# MCU.net
KiCad netlist of a schematic drawn in Altium Designer
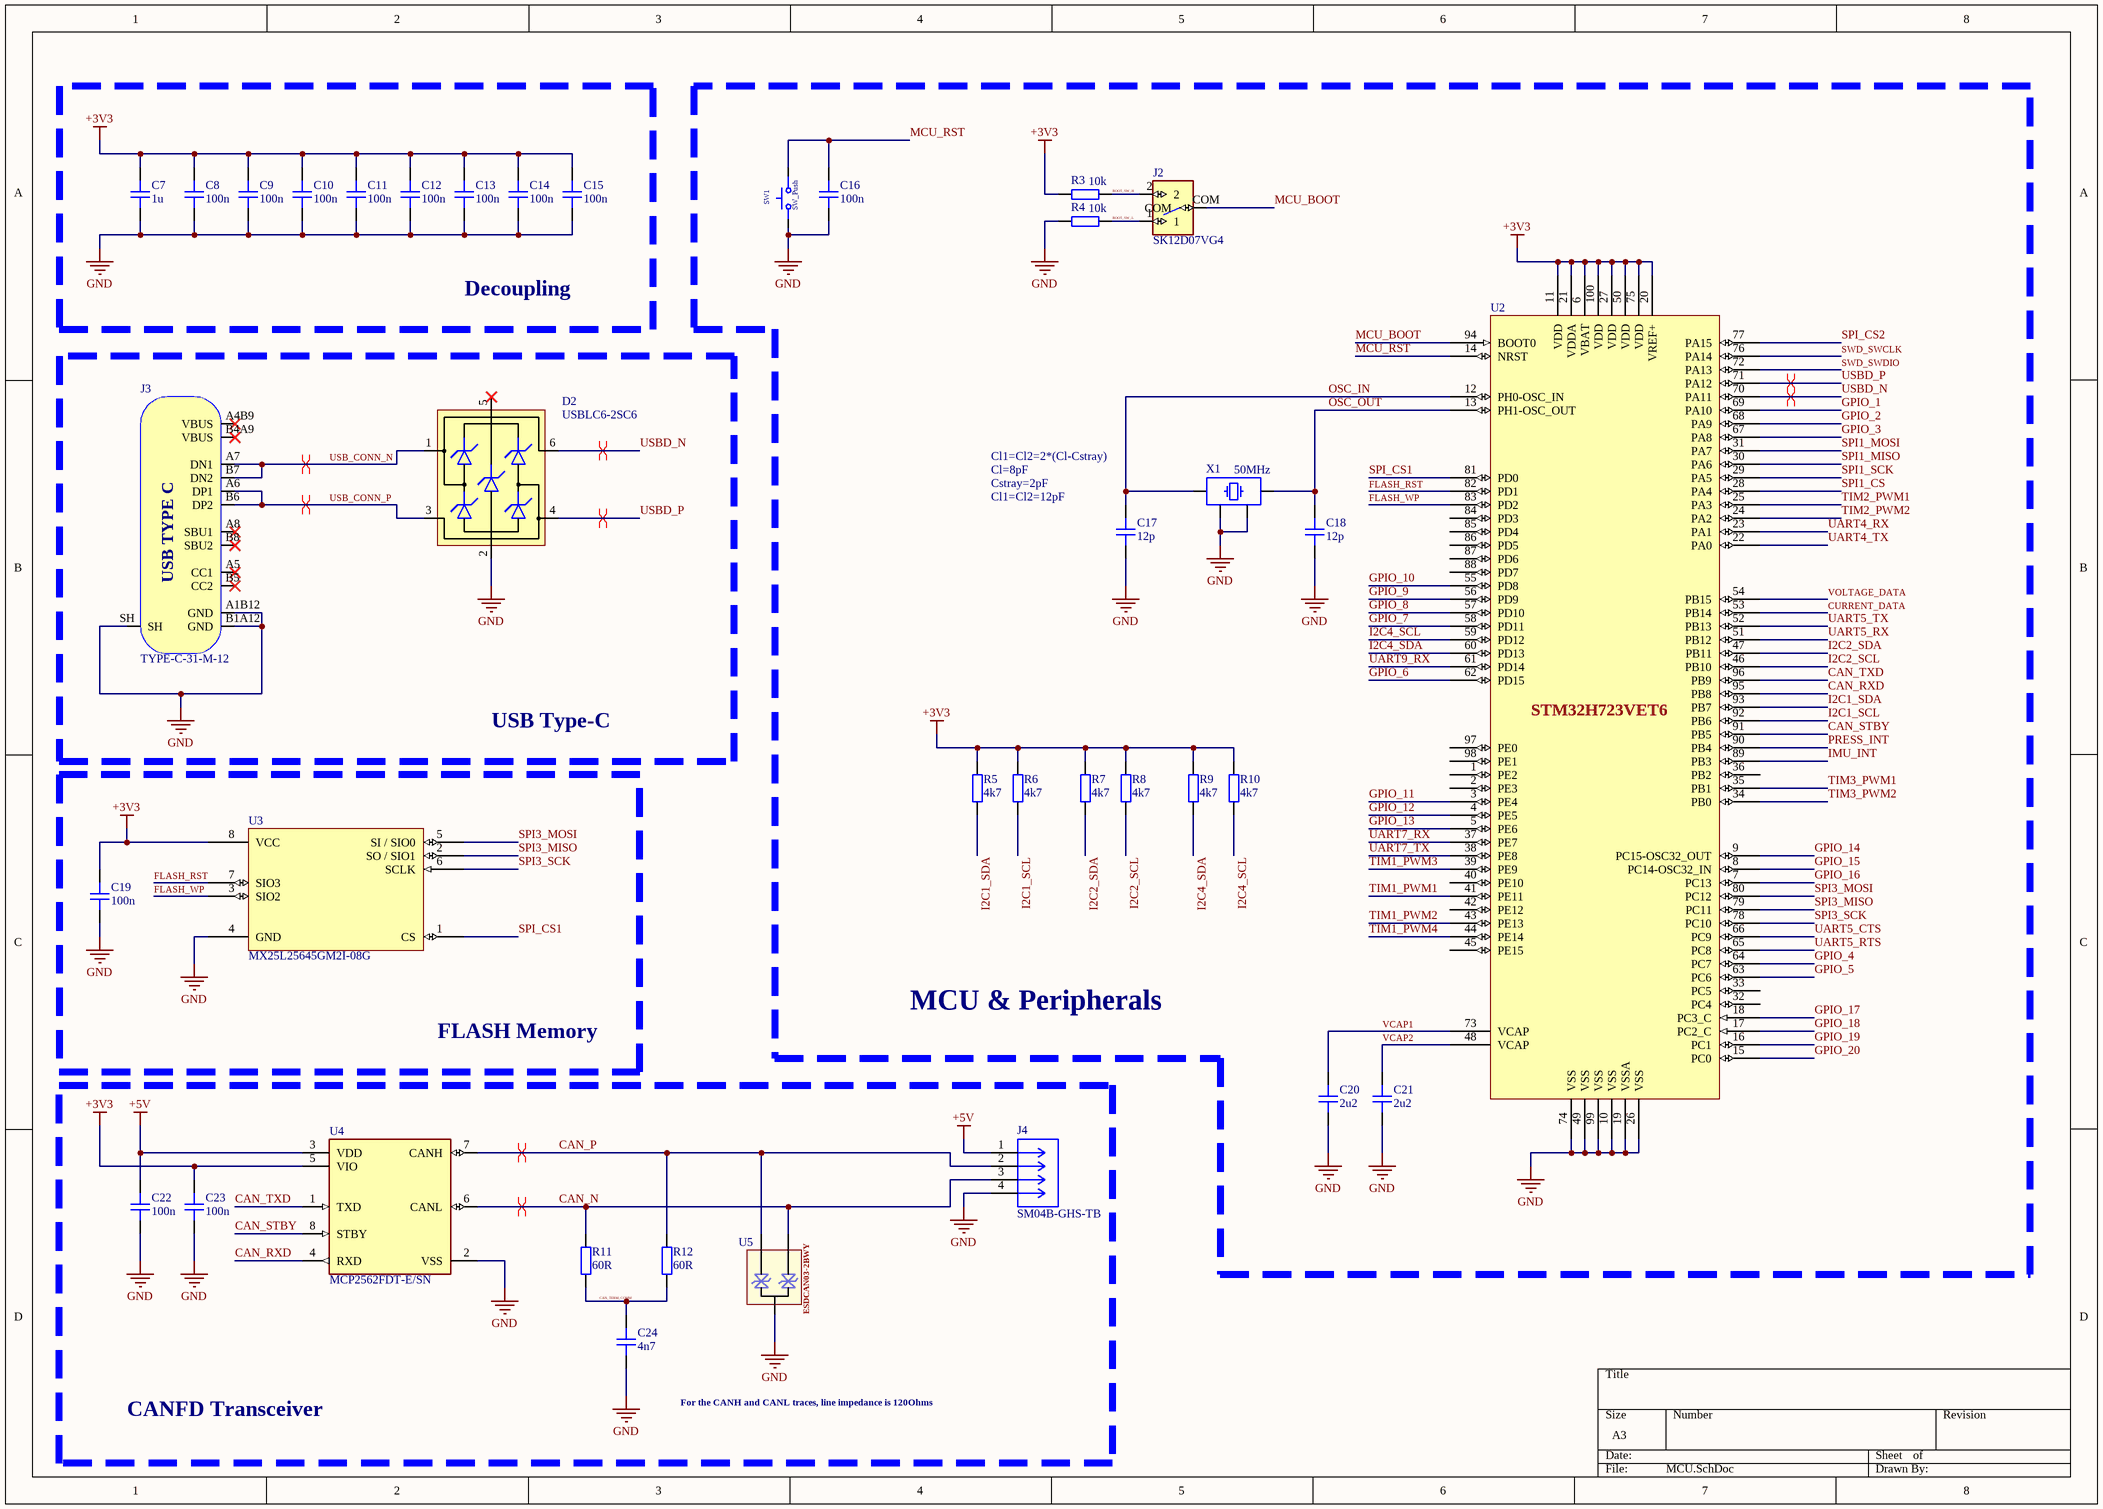
[diagram p0: MCU.SchDoc]

(export (version "E")
  (design (tool "Eeschema 10.0.6"))
  (components
    (comp (ref "C7")
      (value "1u")
      (footprint "CAP_0402")
      (description "Capacitor SMD 0402")
      (libsource (lib "Schematic-Lib-PhilsLab") (part "CAP_0402"))
    )
    (comp (ref "C8")
      (value "100n")
      (footprint "CAP_0402")
      (description "Capacitor SMD 0402")
      (libsource (lib "Schematic-Lib-PhilsLab") (part "CAP_0402"))
    )
    (comp (ref "C9")
      (value "100n")
      (footprint "CAP_0402")
      (description "Capacitor SMD 0402")
      (libsource (lib "Schematic-Lib-PhilsLab") (part "CAP_0402"))
    )
    (comp (ref "C10")
      (value "100n")
      (footprint "CAP_0402")
      (description "Capacitor SMD 0402")
      (libsource (lib "Schematic-Lib-PhilsLab") (part "CAP_0402"))
    )
    (comp (ref "C11")
      (value "100n")
      (footprint "CAP_0402")
      (description "Capacitor SMD 0402")
      (libsource (lib "Schematic-Lib-PhilsLab") (part "CAP_0402"))
    )
    (comp (ref "C12")
      (value "100n")
      (footprint "CAP_0402")
      (description "Capacitor SMD 0402")
      (libsource (lib "Schematic-Lib-PhilsLab") (part "CAP_0402"))
    )
    (comp (ref "C13")
      (value "100n")
      (footprint "CAP_0402")
      (description "Capacitor SMD 0402")
      (libsource (lib "Schematic-Lib-PhilsLab") (part "CAP_0402"))
    )
    (comp (ref "C14")
      (value "100n")
      (footprint "CAP_0402")
      (description "Capacitor SMD 0402")
      (libsource (lib "Schematic-Lib-PhilsLab") (part "CAP_0402"))
    )
    (comp (ref "C15")
      (value "100n")
      (footprint "CAP_0402")
      (description "Capacitor SMD 0402")
      (libsource (lib "Schematic-Lib-PhilsLab") (part "CAP_0402"))
    )
    (comp (ref "C16")
      (value "100n")
      (footprint "CAP_0402")
      (description "Capacitor SMD 0402")
      (libsource (lib "Schematic-Lib-PhilsLab") (part "CAP_0402"))
    )
    (comp (ref "C17")
      (value "12p")
      (footprint "CAP_0402")
      (description "Capacitor SMD 0402")
      (libsource (lib "Schematic-Lib-PhilsLab") (part "CAP_0402"))
    )
    (comp (ref "C18")
      (value "12p")
      (footprint "CAP_0402")
      (description "Capacitor SMD 0402")
      (libsource (lib "Schematic-Lib-PhilsLab") (part "CAP_0402"))
    )
    (comp (ref "C19")
      (value "100n")
      (footprint "CAP_0402")
      (description "Capacitor SMD 0402")
      (libsource (lib "Schematic-Lib-PhilsLab") (part "CAP_0402"))
    )
    (comp (ref "C20")
      (value "2u2")
      (footprint "CAP_0402")
      (description "Capacitor SMD 0402")
      (libsource (lib "Schematic-Lib-PhilsLab") (part "CAP_0402"))
    )
    (comp (ref "C21")
      (value "2u2")
      (footprint "CAP_0402")
      (description "Capacitor SMD 0402")
      (libsource (lib "Schematic-Lib-PhilsLab") (part "CAP_0402"))
    )
    (comp (ref "C22")
      (value "100n")
      (footprint "CAP_0402")
      (description "Capacitor SMD 0402")
      (libsource (lib "Schematic-Lib-PhilsLab") (part "CAP_0402"))
    )
    (comp (ref "C23")
      (value "100n")
      (footprint "CAP_0402")
      (description "Capacitor SMD 0402")
      (libsource (lib "Schematic-Lib-PhilsLab") (part "CAP_0402"))
    )
    (comp (ref "C24")
      (value "4n7")
      (footprint "CAP_0402")
      (description "Capacitor SMD 0402")
      (libsource (lib "Schematic-Lib-PhilsLab") (part "CAP_0402"))
    )
    (comp (ref "D2")
      (value "USBLC6-2SC6")
      (footprint "SOT-23-6")
      (description "Low-Capacitance ESD Protection USB")
      (fields (field (name "MANUFACTURER") "STMicroelectronics"))
      (libsource (lib "Schematic-Lib-PhilsLab") (part "USBLC6-2SC6"))
    )
    (comp (ref "J2")
      (value "SK12D07VG4")
      (footprint "SK12D07VG4")
      (description "Switch Slide ON ON SPDT Side Slide 0.3A 30VDC PC Pins Bracket Mount/Through Hole Bulk")
      (fields (field (name "MF") "C&K"))
      (libsource (lib "SK12D07VG4") (part "SK12D07VG4"))
    )
    (comp (ref "J3")
      (value "TYPE-C-31-M-12")
      (footprint "TYPE-C-31-M-12")
      (description "USB Type C Connector Horizontal SMT")
      (fields (field (name "MANUFACTURER") "Koren Hroparts"))
      (libsource (lib "Schematic-Lib-PhilsLab") (part "TYPE-C-31-M-12"))
    )
    (comp (ref "J4")
      (value "SM04B-GHS-TB")
      (footprint "CONN_SM04B-GHS-TB_JST")
      (description "Connector Header Surface Mount, Right Angle 4 position 0.049 (1.25mm)")
      (fields (field (name "MF") "JST Sales"))
      (libsource (lib "SM04B-GHS-TB") (part "SM04B-GHS-TB"))
    )
    (comp (ref "R3")
      (value "10k")
      (footprint "RES_0402")
      (description "Resistor SMD 0402")
      (libsource (lib "Schematic-Lib-PhilsLab") (part "RES_0402"))
    )
    (comp (ref "R4")
      (value "10k")
      (footprint "RES_0402")
      (description "Resistor SMD 0402")
      (libsource (lib "Schematic-Lib-PhilsLab") (part "RES_0402"))
    )
    (comp (ref "R5")
      (value "4k7")
      (footprint "RES_0402")
      (description "Resistor SMD 0402")
      (libsource (lib "Schematic-Lib-PhilsLab") (part "RES_0402"))
    )
    (comp (ref "R6")
      (value "4k7")
      (footprint "RES_0402")
      (description "Resistor SMD 0402")
      (libsource (lib "Schematic-Lib-PhilsLab") (part "RES_0402"))
    )
    (comp (ref "R7")
      (value "4k7")
      (footprint "RES_0402")
      (description "Resistor SMD 0402")
      (libsource (lib "Schematic-Lib-PhilsLab") (part "RES_0402"))
    )
    (comp (ref "R8")
      (value "4k7")
      (footprint "RES_0402")
      (description "Resistor SMD 0402")
      (libsource (lib "Schematic-Lib-PhilsLab") (part "RES_0402"))
    )
    (comp (ref "R9")
      (value "4k7")
      (footprint "RES_0402")
      (description "Resistor SMD 0402")
      (libsource (lib "Schematic-Lib-PhilsLab") (part "RES_0402"))
    )
    (comp (ref "R10")
      (value "4k7")
      (footprint "RES_0402")
      (description "Resistor SMD 0402")
      (libsource (lib "Schematic-Lib-PhilsLab") (part "RES_0402"))
    )
    (comp (ref "R11")
      (value "60R")
      (footprint "RES_0402")
      (description "Resistor SMD 0402")
      (libsource (lib "Schematic-Lib-PhilsLab") (part "RES_0402"))
    )
    (comp (ref "R12")
      (value "60R")
      (footprint "RES_0402")
      (description "Resistor SMD 0402")
      (libsource (lib "Schematic-Lib-PhilsLab") (part "RES_0402"))
    )
    (comp (ref "SW1")
      (value "SW_Push")
      (footprint "4-PIN BUTTON")
      (libsource (lib "AltiumSchLib") (part "Push Switch"))
    )
    (comp (ref "U2")
      (value "STM32H723VET6")
      (footprint "LQFP100")
      (libsource (lib "AltiumSchLib") (part "STM32H723VET6"))
    )
    (comp (ref "U3")
      (value "MX25L25645GM2I-08G")
      (footprint "SOP8")
      (description "FLASH - NOR Memory IC 256Mbit SPI 120 MHz 8-SOP")
      (libsource (lib "AltiumSchLib") (part "MX25L25673GM2I-08G"))
    )
    (comp (ref "U4")
      (value "MCP2562FDT-E/SN")
      (footprint "FP-C04-057-SN-MFG")
      (description "IC TRANSCEIVER 1/1 8SOIC")
      (libsource (lib "Altium Content Vault") (part "fcb6c66e4429206983adab9201371df"))
    )
    (comp (ref "U5")
      (value "ESDCAN03-2BWY")
      (footprint "SOT65P210X110-3N")
      (libsource (lib "AltiumSchLib") (part "ESDCAN03-2BWY"))
    )
    (comp (ref "X1")
      (value "50MHz")
      (footprint "XTAL_3225")
      (description "WURTH 830108207809")
      (fields
        (field (name "MANUFACTURER") "Epson")
        (field (name "MANUFACTURER PART NUMBER") "TSX-3225 24.0000MF15X-AC")
      )
      (libsource (lib "Schematic-Lib-PhilsLab") (part "TSX-3225_24.0000MF15X-AC"))
    )
  )
  (nets
    (net (code "1") (name "+3V3") (class "Default")
      (node (ref "C10") (pin "2") (pinfunction "2_2") (pintype "passive"))
      (node (ref "C11") (pin "2") (pinfunction "2_2") (pintype "passive"))
      (node (ref "C12") (pin "2") (pinfunction "2_2") (pintype "passive"))
      (node (ref "C13") (pin "2") (pinfunction "2_2") (pintype "passive"))
      (node (ref "C14") (pin "2") (pinfunction "2_2") (pintype "passive"))
      (node (ref "C15") (pin "2") (pinfunction "2_2") (pintype "passive"))
      (node (ref "C19") (pin "2") (pinfunction "2_2") (pintype "passive"))
      (node (ref "C23") (pin "2") (pinfunction "2_2") (pintype "passive"))
      (node (ref "C7") (pin "2") (pinfunction "2_2") (pintype "passive"))
      (node (ref "C8") (pin "2") (pinfunction "2_2") (pintype "passive"))
      (node (ref "C9") (pin "2") (pinfunction "2_2") (pintype "passive"))
      (node (ref "R10") (pin "2") (pinfunction "2_2") (pintype "passive"))
      (node (ref "R3") (pin "1") (pinfunction "1_1") (pintype "passive"))
      (node (ref "R5") (pin "2") (pinfunction "2_2") (pintype "passive"))
      (node (ref "R6") (pin "2") (pinfunction "2_2") (pintype "passive"))
      (node (ref "R7") (pin "2") (pinfunction "2_2") (pintype "passive"))
      (node (ref "R8") (pin "2") (pinfunction "2_2") (pintype "passive"))
      (node (ref "R9") (pin "2") (pinfunction "2_2") (pintype "passive"))
      (node (ref "U2") (pin "100") (pinfunction "VDD_100") (pintype "power_in"))
      (node (ref "U2") (pin "11") (pinfunction "VDD_11") (pintype "power_in"))
      (node (ref "U2") (pin "20") (pinfunction "VREF+_20") (pintype "power_in"))
      (node (ref "U2") (pin "21") (pinfunction "VDDA_21") (pintype "power_in"))
      (node (ref "U2") (pin "27") (pinfunction "VDD_27") (pintype "power_in"))
      (node (ref "U2") (pin "50") (pinfunction "VDD_50") (pintype "power_in"))
      (node (ref "U2") (pin "6") (pinfunction "VBAT_6") (pintype "power_in"))
      (node (ref "U2") (pin "75") (pinfunction "VDD_75") (pintype "power_in"))
      (node (ref "U3") (pin "8") (pinfunction "VCC_8") (pintype "power_in"))
      (node (ref "U4") (pin "5") (pinfunction "VIO_5") (pintype "power_in"))
    )
    (net (code "2") (name "+5V") (class "Default")
      (node (ref "C22") (pin "2") (pinfunction "2_2") (pintype "passive"))
      (node (ref "J4") (pin "1") (pinfunction "1_1") (pintype "passive"))
      (node (ref "U4") (pin "3") (pinfunction "VDD_3") (pintype "power_in"))
    )
    (net (code "3") (name "/BOOT_SW_H") (class "Default")
      (node (ref "J2") (pin "2") (pinfunction "2_2") (pintype "bidirectional"))
      (node (ref "R3") (pin "2") (pinfunction "2_2") (pintype "passive"))
    )
    (net (code "4") (name "/BOOT_SW_L") (class "Default")
      (node (ref "J2") (pin "1") (pinfunction "1_1") (pintype "bidirectional"))
      (node (ref "R4") (pin "2") (pinfunction "2_2") (pintype "passive"))
    )
    (net (code "5") (name "/CAN_N") (class "Default")
      (node (ref "J4") (pin "3") (pinfunction "3_3") (pintype "passive"))
      (node (ref "R11") (pin "2") (pinfunction "2_2") (pintype "passive"))
      (node (ref "U4") (pin "6") (pinfunction "CANL_6") (pintype "bidirectional"))
      (node (ref "U5") (pin "2") (pinfunction "2_2") (pintype "passive"))
    )
    (net (code "6") (name "/CAN_P") (class "Default")
      (node (ref "J4") (pin "2") (pinfunction "2_2") (pintype "passive"))
      (node (ref "R12") (pin "2") (pinfunction "2_2") (pintype "passive"))
      (node (ref "U4") (pin "7") (pinfunction "CANH_7") (pintype "bidirectional"))
      (node (ref "U5") (pin "1") (pinfunction "1_1") (pintype "passive"))
    )
    (net (code "7") (name "/CAN_RXD") (class "Default")
      (node (ref "U2") (pin "95") (pinfunction "PB8_95") (pintype "bidirectional"))
      (node (ref "U4") (pin "4") (pinfunction "RXD_4") (pintype "output"))
    )
    (net (code "8") (name "/CAN_STBY") (class "Default")
      (node (ref "U2") (pin "91") (pinfunction "PB5_91") (pintype "bidirectional"))
      (node (ref "U4") (pin "8") (pinfunction "STBY_8") (pintype "input"))
    )
    (net (code "9") (name "/CAN_TERM_COMM") (class "Default")
      (node (ref "C24") (pin "2") (pinfunction "2_2") (pintype "passive"))
      (node (ref "R11") (pin "1") (pinfunction "1_1") (pintype "passive"))
      (node (ref "R12") (pin "1") (pinfunction "1_1") (pintype "passive"))
    )
    (net (code "10") (name "/CAN_TXD") (class "Default")
      (node (ref "U2") (pin "96") (pinfunction "PB9_96") (pintype "bidirectional"))
      (node (ref "U4") (pin "1") (pinfunction "TXD_1") (pintype "input"))
    )
    (net (code "11") (name "/CURRENT_DATA") (class "Default")
      (node (ref "U2") (pin "53") (pinfunction "PB14_53") (pintype "bidirectional"))
    )
    (net (code "12") (name "/FLASH_RST") (class "Default")
      (node (ref "U2") (pin "82") (pinfunction "PD1_82") (pintype "bidirectional"))
      (node (ref "U3") (pin "7") (pinfunction "SIO3_7") (pintype "bidirectional"))
    )
    (net (code "13") (name "/FLASH_WP") (class "Default")
      (node (ref "U2") (pin "83") (pinfunction "PD2_83") (pintype "bidirectional"))
      (node (ref "U3") (pin "3") (pinfunction "SIO2_3") (pintype "bidirectional"))
    )
    (net (code "14") (name "/GPIO_1") (class "Default")
      (node (ref "U2") (pin "69") (pinfunction "PA10_69") (pintype "bidirectional"))
    )
    (net (code "15") (name "/GPIO_2") (class "Default")
      (node (ref "U2") (pin "68") (pinfunction "PA9_68") (pintype "bidirectional"))
    )
    (net (code "16") (name "/GPIO_3") (class "Default")
      (node (ref "U2") (pin "67") (pinfunction "PA8_67") (pintype "bidirectional"))
    )
    (net (code "17") (name "/GPIO_4") (class "Default")
      (node (ref "U2") (pin "64") (pinfunction "PC7_64") (pintype "bidirectional"))
    )
    (net (code "18") (name "/GPIO_5") (class "Default")
      (node (ref "U2") (pin "63") (pinfunction "PC6_63") (pintype "bidirectional"))
    )
    (net (code "19") (name "/GPIO_6") (class "Default")
      (node (ref "U2") (pin "62") (pinfunction "PD15_62") (pintype "bidirectional"))
    )
    (net (code "20") (name "/GPIO_7") (class "Default")
      (node (ref "U2") (pin "58") (pinfunction "PD11_58") (pintype "bidirectional"))
    )
    (net (code "21") (name "/GPIO_8") (class "Default")
      (node (ref "U2") (pin "57") (pinfunction "PD10_57") (pintype "bidirectional"))
    )
    (net (code "22") (name "/GPIO_9") (class "Default")
      (node (ref "U2") (pin "56") (pinfunction "PD9_56") (pintype "bidirectional"))
    )
    (net (code "23") (name "/GPIO_10") (class "Default")
      (node (ref "U2") (pin "55") (pinfunction "PD8_55") (pintype "bidirectional"))
    )
    (net (code "24") (name "/GPIO_11") (class "Default")
      (node (ref "U2") (pin "3") (pinfunction "PE4_3") (pintype "bidirectional"))
    )
    (net (code "25") (name "/GPIO_12") (class "Default")
      (node (ref "U2") (pin "4") (pinfunction "PE5_4") (pintype "bidirectional"))
    )
    (net (code "26") (name "/GPIO_13") (class "Default")
      (node (ref "U2") (pin "5") (pinfunction "PE6_5") (pintype "bidirectional"))
    )
    (net (code "27") (name "/GPIO_14") (class "Default")
      (node (ref "U2") (pin "9") (pinfunction "PC15-OSC32_OUT_9") (pintype "bidirectional"))
    )
    (net (code "28") (name "/GPIO_15") (class "Default")
      (node (ref "U2") (pin "8") (pinfunction "PC14-OSC32_IN_8") (pintype "bidirectional"))
    )
    (net (code "29") (name "/GPIO_16") (class "Default")
      (node (ref "U2") (pin "7") (pinfunction "PC13_7") (pintype "bidirectional"))
    )
    (net (code "30") (name "/GPIO_17") (class "Default")
      (node (ref "U2") (pin "18") (pinfunction "PC3_C_18") (pintype "input"))
    )
    (net (code "31") (name "/GPIO_18") (class "Default")
      (node (ref "U2") (pin "17") (pinfunction "PC2_C_17") (pintype "input"))
    )
    (net (code "32") (name "/GPIO_19") (class "Default")
      (node (ref "U2") (pin "16") (pinfunction "PC1_16") (pintype "bidirectional"))
    )
    (net (code "33") (name "/GPIO_20") (class "Default")
      (node (ref "U2") (pin "15") (pinfunction "PC0_15") (pintype "bidirectional"))
    )
    (net (code "34") (name "/I2C1_SCL") (class "Default")
      (node (ref "R6") (pin "1") (pinfunction "1_1") (pintype "passive"))
      (node (ref "U2") (pin "92") (pinfunction "PB6_92") (pintype "bidirectional"))
    )
    (net (code "35") (name "/I2C1_SDA") (class "Default")
      (node (ref "R5") (pin "1") (pinfunction "1_1") (pintype "passive"))
      (node (ref "U2") (pin "93") (pinfunction "PB7_93") (pintype "bidirectional"))
    )
    (net (code "36") (name "/I2C2_SCL") (class "Default")
      (node (ref "R8") (pin "1") (pinfunction "1_1") (pintype "passive"))
      (node (ref "U2") (pin "46") (pinfunction "PB10_46") (pintype "bidirectional"))
    )
    (net (code "37") (name "/I2C2_SDA") (class "Default")
      (node (ref "R7") (pin "1") (pinfunction "1_1") (pintype "passive"))
      (node (ref "U2") (pin "47") (pinfunction "PB11_47") (pintype "bidirectional"))
    )
    (net (code "38") (name "/I2C4_SCL") (class "Default")
      (node (ref "R10") (pin "1") (pinfunction "1_1") (pintype "passive"))
      (node (ref "U2") (pin "59") (pinfunction "PD12_59") (pintype "bidirectional"))
    )
    (net (code "39") (name "/I2C4_SDA") (class "Default")
      (node (ref "R9") (pin "1") (pinfunction "1_1") (pintype "passive"))
      (node (ref "U2") (pin "60") (pinfunction "PD13_60") (pintype "bidirectional"))
    )
    (net (code "40") (name "/IMU_INT") (class "Default")
      (node (ref "U2") (pin "89") (pinfunction "PB3_89") (pintype "bidirectional"))
    )
    (net (code "41") (name "/MCU_BOOT") (class "Default")
      (node (ref "J2") (pin "COM") (pinfunction "COM_COM") (pintype "bidirectional"))
      (node (ref "U2") (pin "94") (pinfunction "BOOT0_94") (pintype "input"))
    )
    (net (code "42") (name "/MCU_RST") (class "Default")
      (node (ref "C16") (pin "2") (pinfunction "2_2") (pintype "passive"))
      (node (ref "SW1") (pin "2") (pinfunction "2_2") (pintype "power_in"))
      (node (ref "U2") (pin "14") (pinfunction "NRST_14") (pintype "bidirectional"))
    )
    (net (code "43") (name "/OSC_IN") (class "Default")
      (node (ref "C17") (pin "2") (pinfunction "2_2") (pintype "passive"))
      (node (ref "U2") (pin "12") (pinfunction "PH0-OSC_IN_12") (pintype "bidirectional"))
      (node (ref "X1") (pin "1") (pinfunction "1_1") (pintype "passive"))
    )
    (net (code "44") (name "/OSC_OUT") (class "Default")
      (node (ref "C18") (pin "2") (pinfunction "2_2") (pintype "passive"))
      (node (ref "U2") (pin "13") (pinfunction "PH1-OSC_OUT_13") (pintype "bidirectional"))
      (node (ref "X1") (pin "3") (pinfunction "3_3") (pintype "passive"))
    )
    (net (code "45") (name "/PRESS_INT") (class "Default")
      (node (ref "U2") (pin "90") (pinfunction "PB4_90") (pintype "bidirectional"))
    )
    (net (code "46") (name "/SPI1_CS") (class "Default")
      (node (ref "U2") (pin "28") (pinfunction "PA4_28") (pintype "bidirectional"))
    )
    (net (code "47") (name "/SPI1_MISO") (class "Default")
      (node (ref "U2") (pin "30") (pinfunction "PA6_30") (pintype "bidirectional"))
    )
    (net (code "48") (name "/SPI1_MOSI") (class "Default")
      (node (ref "U2") (pin "31") (pinfunction "PA7_31") (pintype "bidirectional"))
    )
    (net (code "49") (name "/SPI1_SCK") (class "Default")
      (node (ref "U2") (pin "29") (pinfunction "PA5_29") (pintype "bidirectional"))
    )
    (net (code "50") (name "/SPI3_MISO") (class "Default")
      (node (ref "U2") (pin "79") (pinfunction "PC11_79") (pintype "bidirectional"))
      (node (ref "U3") (pin "2") (pinfunction "SO_/_SIO1_2") (pintype "bidirectional"))
    )
    (net (code "51") (name "/SPI3_MOSI") (class "Default")
      (node (ref "U2") (pin "80") (pinfunction "PC12_80") (pintype "bidirectional"))
      (node (ref "U3") (pin "5") (pinfunction "SI_/_SIO0_5") (pintype "bidirectional"))
    )
    (net (code "52") (name "/SPI3_SCK") (class "Default")
      (node (ref "U2") (pin "78") (pinfunction "PC10_78") (pintype "bidirectional"))
      (node (ref "U3") (pin "6") (pinfunction "SCLK_6") (pintype "input"))
    )
    (net (code "53") (name "/SPI_CS1") (class "Default")
      (node (ref "U2") (pin "81") (pinfunction "PD0_81") (pintype "bidirectional"))
      (node (ref "U3") (pin "1") (pinfunction "CS_1") (pintype "bidirectional"))
    )
    (net (code "54") (name "/SPI_CS2") (class "Default")
      (node (ref "U2") (pin "77") (pinfunction "PA15_77") (pintype "bidirectional"))
    )
    (net (code "55") (name "/SWD_SWCLK") (class "Default")
      (node (ref "U2") (pin "76") (pinfunction "PA14_76") (pintype "bidirectional"))
    )
    (net (code "56") (name "/SWD_SWDIO") (class "Default")
      (node (ref "U2") (pin "72") (pinfunction "PA13_72") (pintype "bidirectional"))
    )
    (net (code "57") (name "/TIM1_PWM1") (class "Default")
      (node (ref "U2") (pin "41") (pinfunction "PE11_41") (pintype "bidirectional"))
    )
    (net (code "58") (name "/TIM1_PWM2") (class "Default")
      (node (ref "U2") (pin "43") (pinfunction "PE13_43") (pintype "bidirectional"))
    )
    (net (code "59") (name "/TIM1_PWM3") (class "Default")
      (node (ref "U2") (pin "39") (pinfunction "PE9_39") (pintype "bidirectional"))
    )
    (net (code "60") (name "/TIM1_PWM4") (class "Default")
      (node (ref "U2") (pin "44") (pinfunction "PE14_44") (pintype "bidirectional"))
    )
    (net (code "61") (name "/TIM2_PWM1") (class "Default")
      (node (ref "U2") (pin "25") (pinfunction "PA3_25") (pintype "bidirectional"))
    )
    (net (code "62") (name "/TIM2_PWM2") (class "Default")
      (node (ref "U2") (pin "24") (pinfunction "PA2_24") (pintype "bidirectional"))
    )
    (net (code "63") (name "/TIM3_PWM1") (class "Default")
      (node (ref "U2") (pin "35") (pinfunction "PB1_35") (pintype "bidirectional"))
    )
    (net (code "64") (name "/TIM3_PWM2") (class "Default")
      (node (ref "U2") (pin "34") (pinfunction "PB0_34") (pintype "bidirectional"))
    )
    (net (code "65") (name "/UART4_RX") (class "Default")
      (node (ref "U2") (pin "23") (pinfunction "PA1_23") (pintype "bidirectional"))
    )
    (net (code "66") (name "/UART4_TX") (class "Default")
      (node (ref "U2") (pin "22") (pinfunction "PA0_22") (pintype "bidirectional"))
    )
    (net (code "67") (name "/UART5_CTS") (class "Default")
      (node (ref "U2") (pin "66") (pinfunction "PC9_66") (pintype "bidirectional"))
    )
    (net (code "68") (name "/UART5_RTS") (class "Default")
      (node (ref "U2") (pin "65") (pinfunction "PC8_65") (pintype "bidirectional"))
    )
    (net (code "69") (name "/UART5_RX") (class "Default")
      (node (ref "U2") (pin "51") (pinfunction "PB12_51") (pintype "bidirectional"))
    )
    (net (code "70") (name "/UART5_TX") (class "Default")
      (node (ref "U2") (pin "52") (pinfunction "PB13_52") (pintype "bidirectional"))
    )
    (net (code "71") (name "/UART7_RX") (class "Default")
      (node (ref "U2") (pin "37") (pinfunction "PE7_37") (pintype "bidirectional"))
    )
    (net (code "72") (name "/UART7_TX") (class "Default")
      (node (ref "U2") (pin "38") (pinfunction "PE8_38") (pintype "bidirectional"))
    )
    (net (code "73") (name "/UART9_RX") (class "Default")
      (node (ref "U2") (pin "61") (pinfunction "PD14_61") (pintype "bidirectional"))
    )
    (net (code "74") (name "/USBD_N") (class "Default")
      (node (ref "D2") (pin "6") (pinfunction "IO1_6") (pintype "bidirectional"))
      (node (ref "U2") (pin "70") (pinfunction "PA11_70") (pintype "bidirectional"))
    )
    (net (code "75") (name "/USBD_P") (class "Default")
      (node (ref "D2") (pin "4") (pinfunction "IO2_4") (pintype "bidirectional"))
      (node (ref "U2") (pin "71") (pinfunction "PA12_71") (pintype "bidirectional"))
    )
    (net (code "76") (name "/USB_CONN_N") (class "Default")
      (node (ref "D2") (pin "1") (pinfunction "IO1_1") (pintype "bidirectional"))
      (node (ref "J3") (pin "A7") (pinfunction "DN1_A7") (pintype "bidirectional"))
      (node (ref "J3") (pin "B7") (pinfunction "DN2_B7") (pintype "bidirectional"))
    )
    (net (code "77") (name "/USB_CONN_P") (class "Default")
      (node (ref "D2") (pin "3") (pinfunction "IO2_3") (pintype "bidirectional"))
      (node (ref "J3") (pin "A6") (pinfunction "DP1_A6") (pintype "bidirectional"))
      (node (ref "J3") (pin "B6") (pinfunction "DP2_B6") (pintype "bidirectional"))
    )
    (net (code "78") (name "/VCAP1") (class "Default")
      (node (ref "C20") (pin "2") (pinfunction "2_2") (pintype "passive"))
      (node (ref "U2") (pin "73") (pinfunction "VCAP_73") (pintype "power_in"))
    )
    (net (code "79") (name "/VCAP2") (class "Default")
      (node (ref "C21") (pin "2") (pinfunction "2_2") (pintype "passive"))
      (node (ref "U2") (pin "48") (pinfunction "VCAP_48") (pintype "power_in"))
    )
    (net (code "80") (name "/VOLTAGE_DATA") (class "Default")
      (node (ref "U2") (pin "54") (pinfunction "PB15_54") (pintype "bidirectional"))
    )
    (net (code "81") (name "GND") (class "Default")
      (node (ref "C10") (pin "1") (pinfunction "1_1") (pintype "passive"))
      (node (ref "C11") (pin "1") (pinfunction "1_1") (pintype "passive"))
      (node (ref "C12") (pin "1") (pinfunction "1_1") (pintype "passive"))
      (node (ref "C13") (pin "1") (pinfunction "1_1") (pintype "passive"))
      (node (ref "C14") (pin "1") (pinfunction "1_1") (pintype "passive"))
      (node (ref "C15") (pin "1") (pinfunction "1_1") (pintype "passive"))
      (node (ref "C16") (pin "1") (pinfunction "1_1") (pintype "passive"))
      (node (ref "C17") (pin "1") (pinfunction "1_1") (pintype "passive"))
      (node (ref "C18") (pin "1") (pinfunction "1_1") (pintype "passive"))
      (node (ref "C19") (pin "1") (pinfunction "1_1") (pintype "passive"))
      (node (ref "C20") (pin "1") (pinfunction "1_1") (pintype "passive"))
      (node (ref "C21") (pin "1") (pinfunction "1_1") (pintype "passive"))
      (node (ref "C22") (pin "1") (pinfunction "1_1") (pintype "passive"))
      (node (ref "C23") (pin "1") (pinfunction "1_1") (pintype "passive"))
      (node (ref "C24") (pin "1") (pinfunction "1_1") (pintype "passive"))
      (node (ref "C7") (pin "1") (pinfunction "1_1") (pintype "passive"))
      (node (ref "C8") (pin "1") (pinfunction "1_1") (pintype "passive"))
      (node (ref "C9") (pin "1") (pinfunction "1_1") (pintype "passive"))
      (node (ref "D2") (pin "2") (pinfunction "GND_2") (pintype "power_in"))
      (node (ref "J3") (pin "A1B12") (pinfunction "GND_A1B12") (pintype "power_in"))
      (node (ref "J3") (pin "B1A12") (pinfunction "GND_B1A12") (pintype "power_in"))
      (node (ref "J3") (pin "SH") (pinfunction "SH_SH") (pintype "power_in"))
      (node (ref "J4") (pin "4") (pinfunction "4_4") (pintype "passive"))
      (node (ref "R4") (pin "1") (pinfunction "1_1") (pintype "passive"))
      (node (ref "SW1") (pin "1") (pinfunction "1_1") (pintype "power_in"))
      (node (ref "U2") (pin "10") (pinfunction "VSS_10") (pintype "power_in"))
      (node (ref "U2") (pin "19") (pinfunction "VSSA_19") (pintype "power_in"))
      (node (ref "U2") (pin "26") (pinfunction "VSS_26") (pintype "power_in"))
      (node (ref "U2") (pin "49") (pinfunction "VSS_49") (pintype "power_in"))
      (node (ref "U2") (pin "74") (pinfunction "VSS_74") (pintype "power_in"))
      (node (ref "U2") (pin "99") (pinfunction "VSS_99") (pintype "power_in"))
      (node (ref "U3") (pin "4") (pinfunction "GND_4") (pintype "power_in"))
      (node (ref "U4") (pin "2") (pinfunction "VSS_2") (pintype "power_in"))
      (node (ref "U5") (pin "3") (pinfunction "3_3") (pintype "power_in"))
      (node (ref "X1") (pin "2") (pinfunction "2_2") (pintype "passive"))
      (node (ref "X1") (pin "4") (pinfunction "4_4") (pintype "passive"))
    )
    (net (code "82") (name "unconnected-(D2-VBUS-Pad5)") (class "Default")
      (node (ref "D2") (pin "5") (pinfunction "VBUS_5") (pintype "power_in+no_connect"))
    )
    (net (code "83") (name "unconnected-(J3-CC1-PadA5)") (class "Default")
      (node (ref "J3") (pin "A5") (pinfunction "CC1_A5") (pintype "passive+no_connect"))
    )
    (net (code "84") (name "unconnected-(J3-CC2-PadB5)") (class "Default")
      (node (ref "J3") (pin "B5") (pinfunction "CC2_B5") (pintype "tri_state+no_connect"))
    )
    (net (code "85") (name "unconnected-(J3-SBU1-PadA8)") (class "Default")
      (node (ref "J3") (pin "A8") (pinfunction "SBU1_A8") (pintype "bidirectional+no_connect"))
    )
    (net (code "86") (name "unconnected-(J3-SBU2-PadB8)") (class "Default")
      (node (ref "J3") (pin "B8") (pinfunction "SBU2_B8") (pintype "bidirectional+no_connect"))
    )
    (net (code "87") (name "unconnected-(J3-VBUS-PadA4B9)") (class "Default")
      (node (ref "J3") (pin "A4B9") (pinfunction "VBUS_A4B9") (pintype "power_in+no_connect"))
    )
    (net (code "88") (name "unconnected-(J3-VBUS-PadB4A9)") (class "Default")
      (node (ref "J3") (pin "B4A9") (pinfunction "VBUS_B4A9") (pintype "power_in+no_connect"))
    )
    (net (code "89") (name "unconnected-(U2-PB2-Pad36)") (class "Default")
      (node (ref "U2") (pin "36") (pinfunction "PB2_36") (pintype "bidirectional"))
    )
    (net (code "90") (name "unconnected-(U2-PC4-Pad32)") (class "Default")
      (node (ref "U2") (pin "32") (pinfunction "PC4_32") (pintype "bidirectional"))
    )
    (net (code "91") (name "unconnected-(U2-PC5-Pad33)") (class "Default")
      (node (ref "U2") (pin "33") (pinfunction "PC5_33") (pintype "bidirectional"))
    )
    (net (code "92") (name "unconnected-(U2-PD3-Pad84)") (class "Default")
      (node (ref "U2") (pin "84") (pinfunction "PD3_84") (pintype "bidirectional"))
    )
    (net (code "93") (name "unconnected-(U2-PD4-Pad85)") (class "Default")
      (node (ref "U2") (pin "85") (pinfunction "PD4_85") (pintype "bidirectional"))
    )
    (net (code "94") (name "unconnected-(U2-PD5-Pad86)") (class "Default")
      (node (ref "U2") (pin "86") (pinfunction "PD5_86") (pintype "bidirectional"))
    )
    (net (code "95") (name "unconnected-(U2-PD6-Pad87)") (class "Default")
      (node (ref "U2") (pin "87") (pinfunction "PD6_87") (pintype "bidirectional"))
    )
    (net (code "96") (name "unconnected-(U2-PD7-Pad88)") (class "Default")
      (node (ref "U2") (pin "88") (pinfunction "PD7_88") (pintype "bidirectional"))
    )
    (net (code "97") (name "unconnected-(U2-PE0-Pad97)") (class "Default")
      (node (ref "U2") (pin "97") (pinfunction "PE0_97") (pintype "bidirectional"))
    )
    (net (code "98") (name "unconnected-(U2-PE1-Pad98)") (class "Default")
      (node (ref "U2") (pin "98") (pinfunction "PE1_98") (pintype "bidirectional"))
    )
    (net (code "99") (name "unconnected-(U2-PE2-Pad1)") (class "Default")
      (node (ref "U2") (pin "1") (pinfunction "PE2_1") (pintype "bidirectional"))
    )
    (net (code "100") (name "unconnected-(U2-PE3-Pad2)") (class "Default")
      (node (ref "U2") (pin "2") (pinfunction "PE3_2") (pintype "bidirectional"))
    )
    (net (code "101") (name "unconnected-(U2-PE10-Pad40)") (class "Default")
      (node (ref "U2") (pin "40") (pinfunction "PE10_40") (pintype "bidirectional"))
    )
    (net (code "102") (name "unconnected-(U2-PE12-Pad42)") (class "Default")
      (node (ref "U2") (pin "42") (pinfunction "PE12_42") (pintype "bidirectional"))
    )
    (net (code "103") (name "unconnected-(U2-PE15-Pad45)") (class "Default")
      (node (ref "U2") (pin "45") (pinfunction "PE15_45") (pintype "bidirectional"))
    )
  )
)
